# Private_CPU_SerDes.net
KiCad netlist of a schematic drawn in Altium Designer
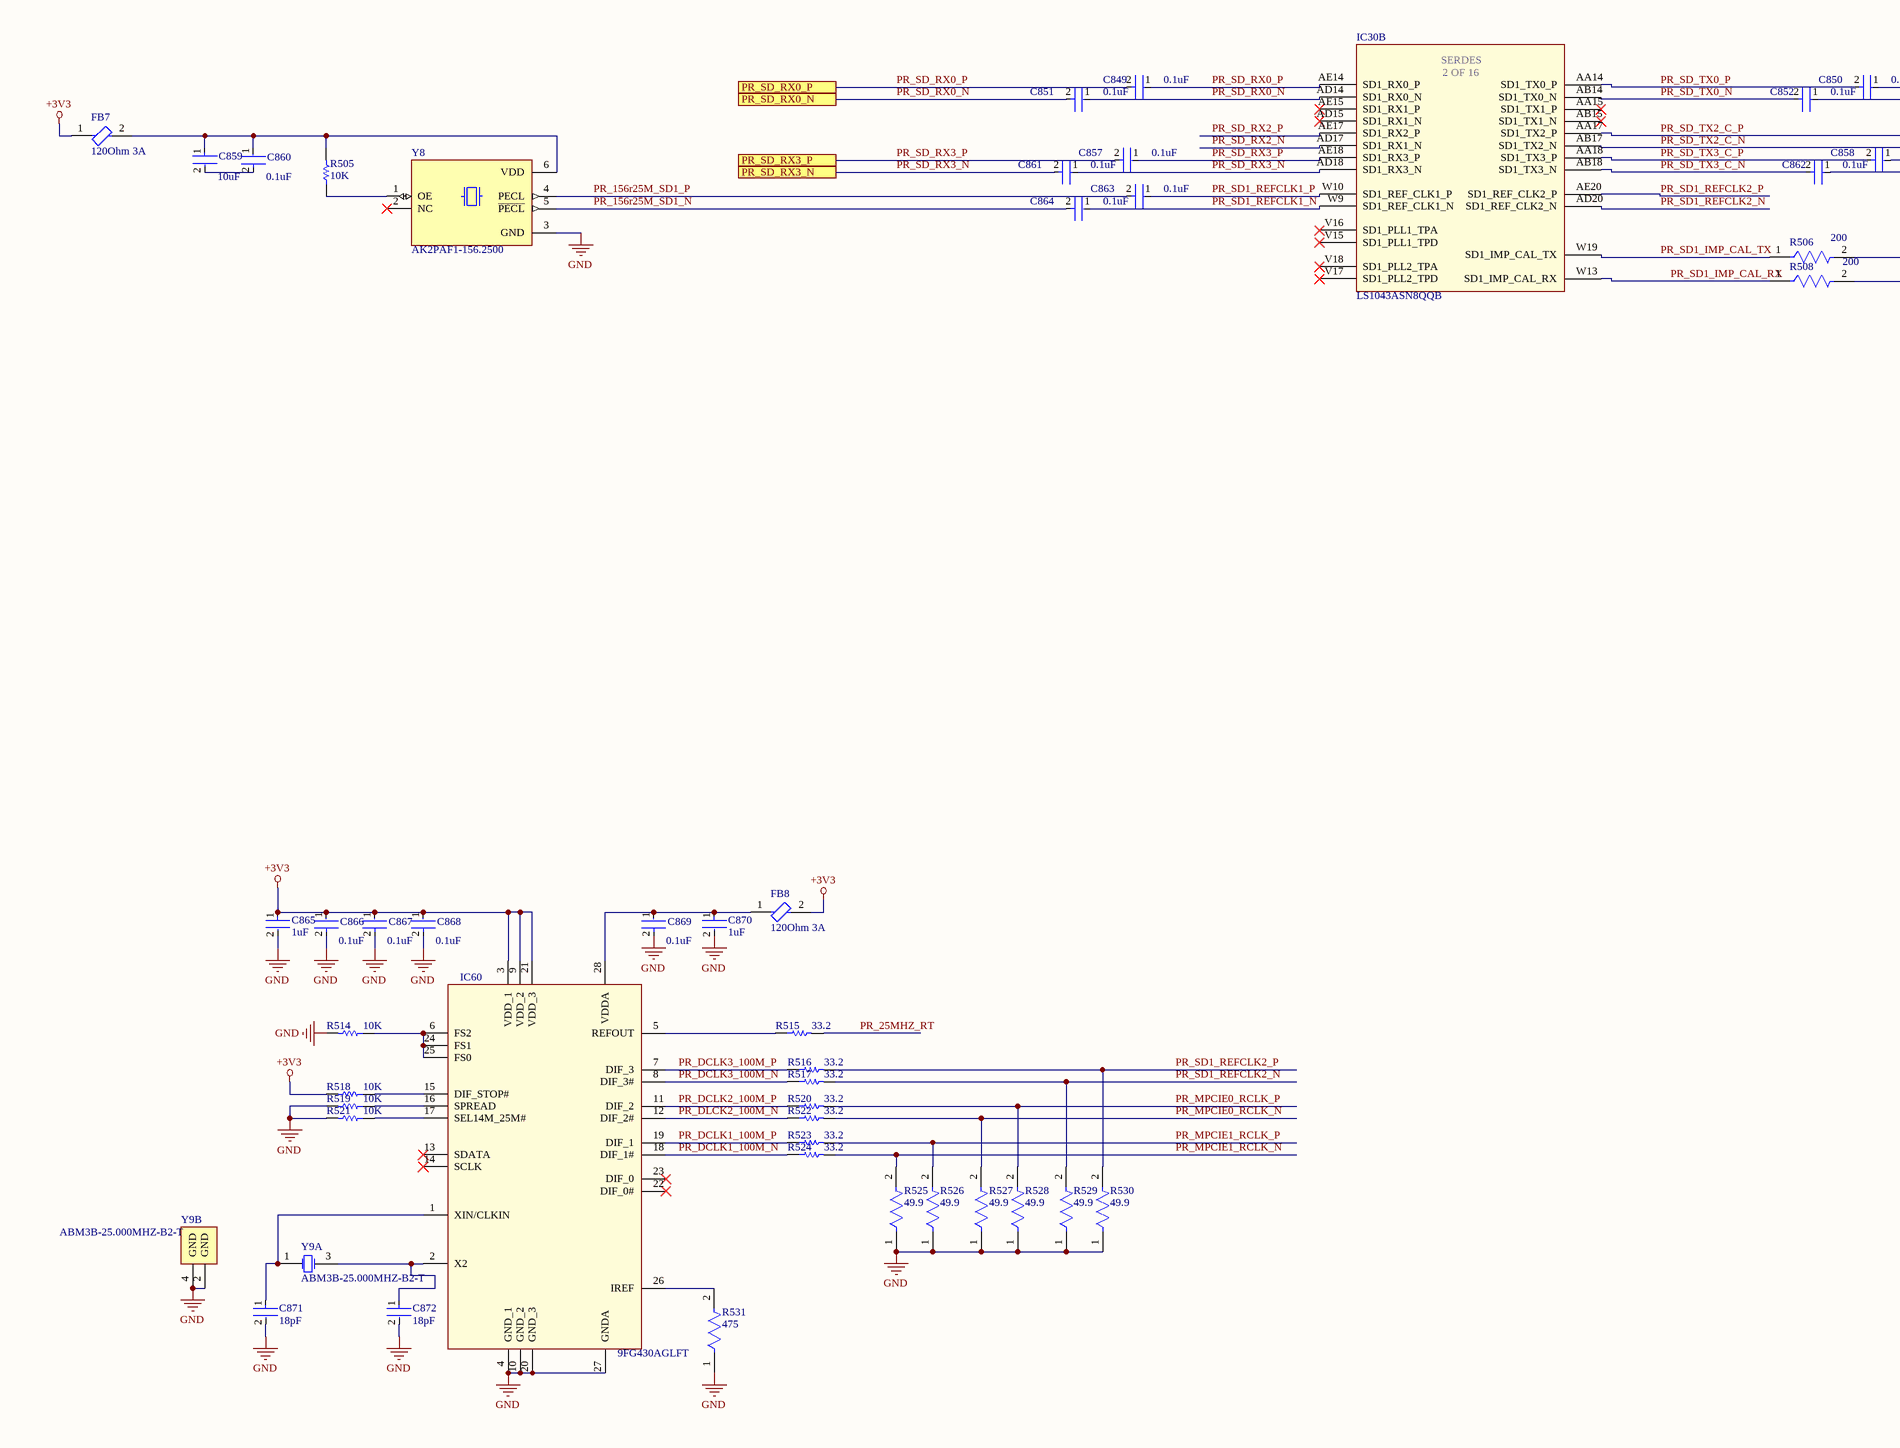
[diagram p0: Private_CPU_SerDes.SchDoc, left]
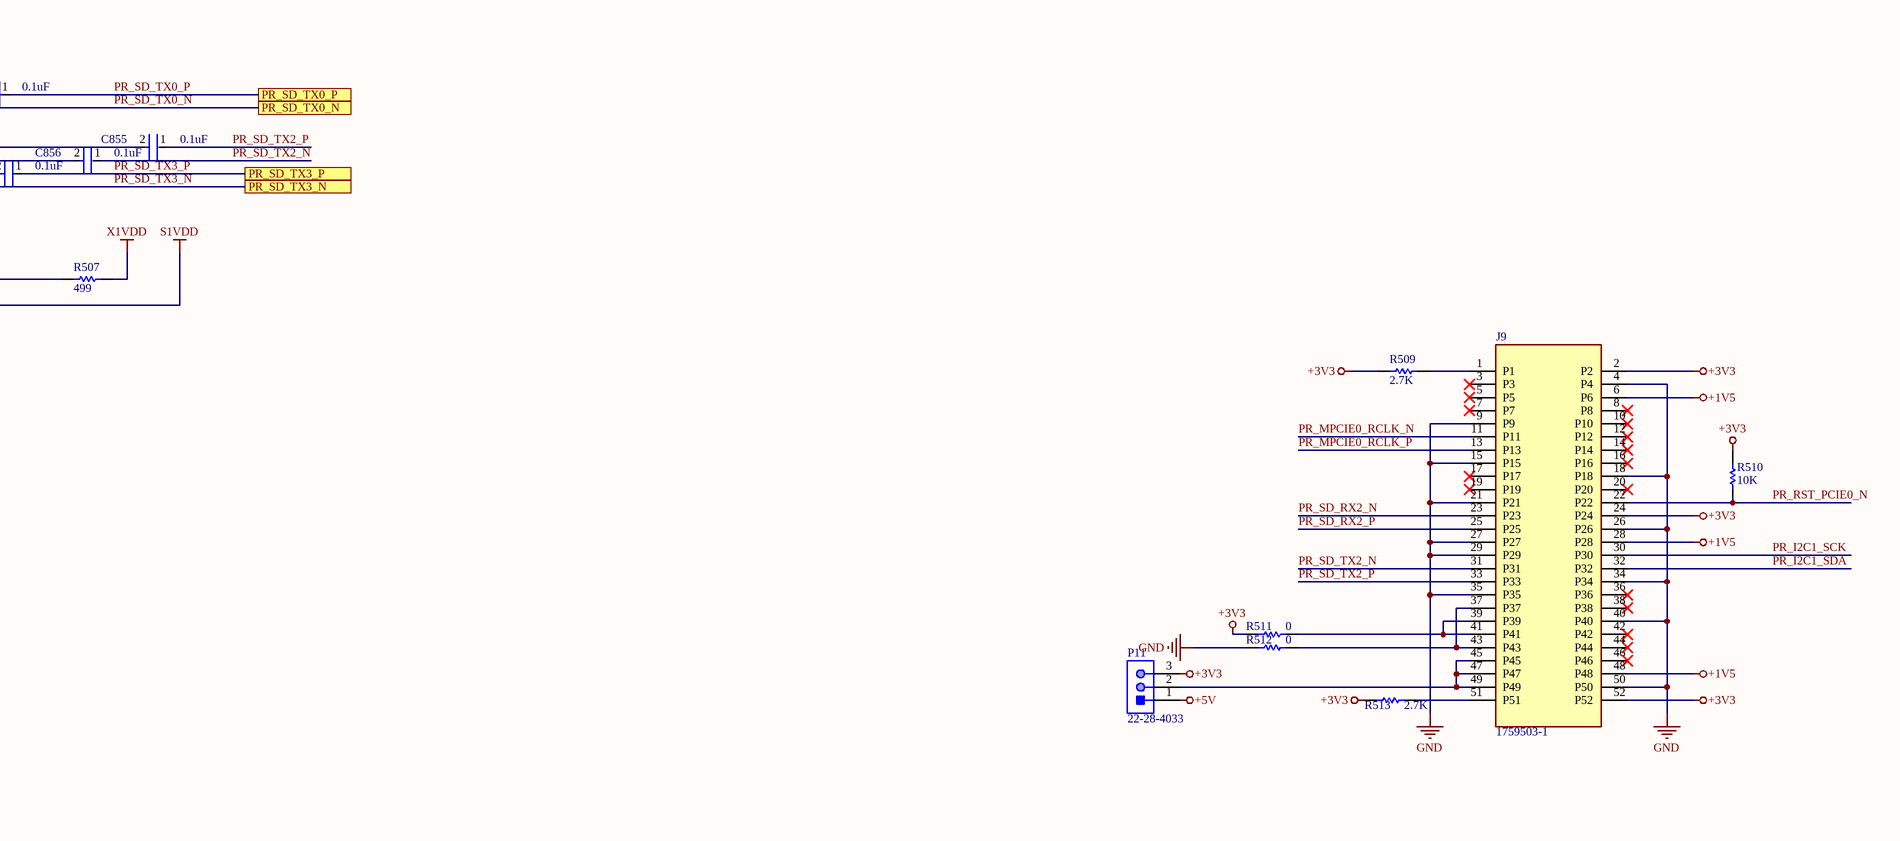
[diagram p1: Private_CPU_SerDes.SchDoc, right]

(export (version "E")
  (design (tool "Eeschema 10.0.6"))
  (components
    (comp (ref "C849")
      (value "0.1uF")
      (footprint "FP-GRM15-MFG")
      (description "CAP CER 0.1UF 16V X7R 0402")
      (fields (field (name "MANUFACTURER PART NUMBER") "GRM155R71C104KA88D") (field (name "TOLERANCE") "10%"))
      (libsource (lib "Altium Content Vault") (part "236180d848d6139a670b325ea6854c9"))
    )
    (comp (ref "C850")
      (value "0.1uF")
      (footprint "FP-GRM15-MFG")
      (description "CAP CER 0.1UF 16V X7R 0402")
      (fields (field (name "MANUFACTURER PART NUMBER") "GRM155R71C104KA88D") (field (name "TOLERANCE") "10%"))
      (libsource (lib "Altium Content Vault") (part "236180d848d6139a670b325ea6854c9"))
    )
    (comp (ref "C851")
      (value "0.1uF")
      (footprint "FP-GRM15-MFG")
      (description "CAP CER 0.1UF 16V X7R 0402")
      (fields (field (name "MANUFACTURER PART NUMBER") "GRM155R71C104KA88D") (field (name "TOLERANCE") "10%"))
      (libsource (lib "Altium Content Vault") (part "236180d848d6139a670b325ea6854c9"))
    )
    (comp (ref "C852")
      (value "0.1uF")
      (footprint "FP-GRM15-MFG")
      (description "CAP CER 0.1UF 16V X7R 0402")
      (fields (field (name "MANUFACTURER PART NUMBER") "GRM155R71C104KA88D") (field (name "TOLERANCE") "10%"))
      (libsource (lib "Altium Content Vault") (part "236180d848d6139a670b325ea6854c9"))
    )
    (comp (ref "C855")
      (value "0.1uF")
      (footprint "FP-GRM15-MFG")
      (description "CAP CER 0.1UF 16V X7R 0402")
      (fields (field (name "MANUFACTURER PART NUMBER") "GRM155R71C104KA88D") (field (name "TOLERANCE") "10%"))
      (libsource (lib "Altium Content Vault") (part "236180d848d6139a670b325ea6854c9"))
    )
    (comp (ref "C856")
      (value "0.1uF")
      (footprint "FP-GRM15-MFG")
      (description "CAP CER 0.1UF 16V X7R 0402")
      (fields (field (name "MANUFACTURER PART NUMBER") "GRM155R71C104KA88D") (field (name "TOLERANCE") "10%"))
      (libsource (lib "Altium Content Vault") (part "236180d848d6139a670b325ea6854c9"))
    )
    (comp (ref "C857")
      (value "0.1uF")
      (footprint "FP-GRM15-MFG")
      (description "CAP CER 0.1UF 16V X7R 0402")
      (fields (field (name "MANUFACTURER PART NUMBER") "GRM155R71C104KA88D") (field (name "TOLERANCE") "10%"))
      (libsource (lib "Altium Content Vault") (part "236180d848d6139a670b325ea6854c9"))
    )
    (comp (ref "C858")
      (value "0.1uF")
      (footprint "FP-GRM15-MFG")
      (description "CAP CER 0.1UF 16V X7R 0402")
      (fields (field (name "MANUFACTURER PART NUMBER") "GRM155R71C104KA88D") (field (name "TOLERANCE") "10%"))
      (libsource (lib "Altium Content Vault") (part "236180d848d6139a670b325ea6854c9"))
    )
    (comp (ref "C859")
      (value "10uF")
      (footprint "FP-C0805C-DG-MFG")
      (description "CAP CER 10UF 10V X5R 0805")
      (fields (field (name "TOLERANCE") "10%") (field (name "MANUFACTURER PART NUMBER") "C0805C106K8PACTU"))
      (libsource (lib "Altium Content Vault") (part "11868f565c42a9108669ba33697ecf6"))
    )
    (comp (ref "C860")
      (value "0.1uF")
      (footprint "FP-GRM15-MFG")
      (description "CAP CER 0.1UF 16V X7R 0402")
      (fields (field (name "MANUFACTURER PART NUMBER") "GRM155R71C104KA88D") (field (name "TOLERANCE") "10%"))
      (libsource (lib "Altium Content Vault") (part "236180d848d6139a670b325ea6854c9"))
    )
    (comp (ref "C861")
      (value "0.1uF")
      (footprint "FP-GRM15-MFG")
      (description "CAP CER 0.1UF 16V X7R 0402")
      (fields (field (name "MANUFACTURER PART NUMBER") "GRM155R71C104KA88D") (field (name "TOLERANCE") "10%"))
      (libsource (lib "Altium Content Vault") (part "236180d848d6139a670b325ea6854c9"))
    )
    (comp (ref "C862")
      (value "0.1uF")
      (footprint "FP-GRM15-MFG")
      (description "CAP CER 0.1UF 16V X7R 0402")
      (fields (field (name "MANUFACTURER PART NUMBER") "GRM155R71C104KA88D") (field (name "TOLERANCE") "10%"))
      (libsource (lib "Altium Content Vault") (part "236180d848d6139a670b325ea6854c9"))
    )
    (comp (ref "C863")
      (value "0.1uF")
      (footprint "FP-GRM15-MFG")
      (description "CAP CER 0.1UF 16V X7R 0402")
      (fields (field (name "MANUFACTURER PART NUMBER") "GRM155R71C104KA88D") (field (name "TOLERANCE") "10%"))
      (libsource (lib "Altium Content Vault") (part "236180d848d6139a670b325ea6854c9"))
    )
    (comp (ref "C864")
      (value "0.1uF")
      (footprint "FP-GRM15-MFG")
      (description "CAP CER 0.1UF 16V X7R 0402")
      (fields (field (name "MANUFACTURER PART NUMBER") "GRM155R71C104KA88D") (field (name "TOLERANCE") "10%"))
      (libsource (lib "Altium Content Vault") (part "236180d848d6139a670b325ea6854c9"))
    )
    (comp (ref "C865")
      (value "1uF")
      (footprint "FP-GRM15-0_1-MFG")
      (description "CAP CER 1UF 10V X5R 0402")
      (fields
        (field (name "OCTOPART") "https://octopart.com/grm155r61a105ke15d-murata-197442")
        (field (name "MANUFACTURER PART NUMBER") "GRM155R61A105KE15D")
      )
      (libsource (lib "Altium Content Vault") (part "02cd4be3c70576c341d710602a673aa"))
    )
    (comp (ref "C866")
      (value "0.1uF")
      (footprint "FP-GRM15-MFG")
      (description "CAP CER 0.1UF 16V X7R 0402")
      (fields (field (name "MANUFACTURER PART NUMBER") "GRM155R71C104KA88D") (field (name "TOLERANCE") "10%"))
      (libsource (lib "Altium Content Vault") (part "236180d848d6139a670b325ea6854c9"))
    )
    (comp (ref "C867")
      (value "0.1uF")
      (footprint "FP-GRM15-MFG")
      (description "CAP CER 0.1UF 16V X7R 0402")
      (fields (field (name "MANUFACTURER PART NUMBER") "GRM155R71C104KA88D") (field (name "TOLERANCE") "10%"))
      (libsource (lib "Altium Content Vault") (part "236180d848d6139a670b325ea6854c9"))
    )
    (comp (ref "C868")
      (value "0.1uF")
      (footprint "FP-GRM15-MFG")
      (description "CAP CER 0.1UF 16V X7R 0402")
      (fields (field (name "MANUFACTURER PART NUMBER") "GRM155R71C104KA88D") (field (name "TOLERANCE") "10%"))
      (libsource (lib "Altium Content Vault") (part "236180d848d6139a670b325ea6854c9"))
    )
    (comp (ref "C869")
      (value "0.1uF")
      (footprint "FP-GRM15-MFG")
      (description "CAP CER 0.1UF 16V X7R 0402")
      (fields (field (name "MANUFACTURER PART NUMBER") "GRM155R71C104KA88D") (field (name "TOLERANCE") "10%"))
      (libsource (lib "Altium Content Vault") (part "236180d848d6139a670b325ea6854c9"))
    )
    (comp (ref "C870")
      (value "1uF")
      (footprint "FP-GRM15-0_1-MFG")
      (description "CAP CER 1UF 10V X5R 0402")
      (fields
        (field (name "OCTOPART") "https://octopart.com/grm155r61a105ke15d-murata-197442")
        (field (name "MANUFACTURER PART NUMBER") "GRM155R61A105KE15D")
      )
      (libsource (lib "Altium Content Vault") (part "02cd4be3c70576c341d710602a673aa"))
    )
    (comp (ref "C871")
      (value "18pF")
      (footprint "FP-C0402-BB-MFG")
      (description "CAP CER 18PF 50V 5% NP0 0402")
      (fields (field (name "MANUFACTURER PART NUMBER") "C0402C180J5GACTU") (field (name "TOLERANCE") "0.05"))
      (libsource (lib "Altium Content Vault") (part "b4654b650e69147ec39a6b967a45e02"))
    )
    (comp (ref "C872")
      (value "18pF")
      (footprint "FP-C0402-BB-MFG")
      (description "CAP CER 18PF 50V 5% NP0 0402")
      (fields (field (name "MANUFACTURER PART NUMBER") "C0402C180J5GACTU") (field (name "TOLERANCE") "0.05"))
      (libsource (lib "Altium Content Vault") (part "b4654b650e69147ec39a6b967a45e02"))
    )
    (comp (ref "FB7")
      (value "120Ohm 3A")
      (footprint "FP-BLM18-0_15-t0_5-d1_2-MFG")
      (description "Chip Ferrite Bead, 0603, 120Ω @ 100MHz, 25%, 0.025Ω, 3A")
      (fields (field (name "TOLERANCE") "25%"))
      (libsource (lib "Altium Content Vault") (part "5f30dd21d616792df468990f7003faa"))
    )
    (comp (ref "FB8")
      (value "120Ohm 3A")
      (footprint "FP-BLM18-0_15-t0_5-d1_2-MFG")
      (description "Chip Ferrite Bead, 0603, 120Ω @ 100MHz, 25%, 0.025Ω, 3A")
      (fields (field (name "TOLERANCE") "25%"))
      (libsource (lib "Altium Content Vault") (part "5f30dd21d616792df468990f7003faa"))
    )
    (comp (ref "IC30")
      (value "LS1043ASN8QQB")
      (footprint "SamacSys:BGA780C80P28X28_2300X2300X261")
      (description "Integrated Circuit")
      (fields (field (name "MOUSER PART NUMBER") "771-LS1043ASN8QQB"))
      (libsource (lib "SamacSys") (part "LS1043ASN8QQB"))
    )
    (comp (ref "IC60")
      (value "9FG430AGLFT")
      (footprint "SamacSys:SOP65P640X120-28N")
      (description "Integrated Circuit")
      (libsource (lib "SamacSys") (part "9FG430AGLFT"))
    )
    (comp (ref "J9")
      (value "1759503-1")
      (footprint "1759503-1:TE_1759503-1")
      (description "mini PCI-E 8H Type I PKG G/F")
      (fields (field (name "MF") "{'manufacturer': u'TE Connectivity'}"))
      (libsource (lib "*") (part "1759503-1"))
    )
    (comp (ref "P11")
      (value "22-28-4033")
      (footprint "MOLX-22-28-4033_V")
      (description "Male Header, Pitch 2.54 mm, 1 x 3 Position, Height 8.38 mm, Tail Length 3.18 mm, RoHS, Bulk")
      (fields (field (name "MANUFACTURER") "Molex"))
      (libsource (lib "Altium Content Vault") (part "CN-1P-M-R3"))
    )
    (comp (ref "R505")
      (value "10K")
      (footprint "RESC1005X40X25LL05T05")
      (description "Chip Resistor, 10 KOhm, +/- 1%, 0.1 W, -55 to 155 degC, 0402 (1005 Metric), RoHS, Tape and Reel")
      (fields (field (name "TOLERANCE") "1%") (field (name "MANUFACTURER") "Panasonic"))
      (libsource (lib "Altium Content Vault") (part "RES-2"))
    )
    (comp (ref "R506")
      (value "200")
      (footprint "FP-CRCW0402-e3-IPC_C")
      (description "RES Thick Film, 200Ω, 1%, 0.063W, 100ppm/°C, 0402")
      (fields (field (name "TOLERANCE") "1%"))
      (libsource (lib "Altium Content Vault") (part "1029c3af85768c4190bb7ad29bc67b5"))
    )
    (comp (ref "R507")
      (value "499")
      (footprint "RESC1005X40X25LL05T05")
      (fields (field (name "MANUFACTURER") "Panasonic") (field (name "PART NUMBER") "ERJ-2RKF4990X"))
      (libsource (lib "Altium Content Vault") (part "RES"))
    )
    (comp (ref "R508")
      (value "200")
      (footprint "FP-CRCW0402-e3-IPC_C")
      (description "RES Thick Film, 200Ω, 1%, 0.063W, 100ppm/°C, 0402")
      (fields (field (name "TOLERANCE") "1%"))
      (libsource (lib "Altium Content Vault") (part "1029c3af85768c4190bb7ad29bc67b5"))
    )
    (comp (ref "R509")
      (value "2.7K")
      (footprint "RESC1005X40X25NL05T05")
      (fields (field (name "PART NUMBER") "ERJ2RKF2701X") (field (name "MANUFACTURER") "Panasonic"))
      (libsource (lib "Altium Content Vault") (part "RES"))
    )
    (comp (ref "R510")
      (value "10K")
      (footprint "RESC1005X40X25LL05T05")
      (description "Chip Resistor, 10 KOhm, +/- 1%, 0.1 W, -55 to 155 degC, 0402 (1005 Metric), RoHS, Tape and Reel")
      (fields (field (name "TOLERANCE") "1%") (field (name "MANUFACTURER") "Panasonic"))
      (libsource (lib "Altium Content Vault") (part "RES-2"))
    )
    (comp (ref "R511")
      (value "0")
      (footprint "RESC2013X50X30LL20T20")
      (fields (field (name "MANUFACTURER") "Vishay Dale") (field (name "PART NUMBER") "CRCW08050000Z0EA"))
      (libsource (lib "Altium Content Vault") (part "RES"))
    )
    (comp (ref "R512")
      (value "0")
      (footprint "RESC2013X50X30LL20T20")
      (fields (field (name "MANUFACTURER") "Vishay Dale") (field (name "PART NUMBER") "CRCW08050000Z0EA"))
      (libsource (lib "Altium Content Vault") (part "RES"))
    )
    (comp (ref "R513")
      (value "2.7K")
      (footprint "RESC1005X40X25NL05T05")
      (fields (field (name "PART NUMBER") "ERJ2RKF2701X") (field (name "MANUFACTURER") "Panasonic"))
      (libsource (lib "Altium Content Vault") (part "RES"))
    )
    (comp (ref "R514")
      (value "10K")
      (footprint "RESC1005X40X25LL05T05")
      (description "Chip Resistor, 10 KOhm, +/- 1%, 0.1 W, -55 to 155 degC, 0402 (1005 Metric), RoHS, Tape and Reel")
      (fields (field (name "TOLERANCE") "1%") (field (name "MANUFACTURER") "Panasonic"))
      (libsource (lib "Altium Content Vault") (part "RES-2"))
    )
    (comp (ref "R515")
      (value "33.2")
      (footprint "RESC1005X40X25LL05T05")
      (fields (field (name "PART NUMBER") "CRCW040233R2FKED") (field (name "MANUFACTURER") "Vishay Dale"))
      (libsource (lib "Altium Content Vault") (part "RES"))
    )
    (comp (ref "R516")
      (value "33.2")
      (footprint "RESC1005X40X25LL05T05")
      (fields (field (name "PART NUMBER") "CRCW040233R2FKED") (field (name "MANUFACTURER") "Vishay Dale"))
      (libsource (lib "Altium Content Vault") (part "RES"))
    )
    (comp (ref "R517")
      (value "33.2")
      (footprint "RESC1005X40X25LL05T05")
      (fields (field (name "PART NUMBER") "CRCW040233R2FKED") (field (name "MANUFACTURER") "Vishay Dale"))
      (libsource (lib "Altium Content Vault") (part "RES"))
    )
    (comp (ref "R518")
      (value "10K")
      (footprint "RESC1005X40X25LL05T05")
      (description "Chip Resistor, 10 KOhm, +/- 1%, 0.1 W, -55 to 155 degC, 0402 (1005 Metric), RoHS, Tape and Reel")
      (fields (field (name "TOLERANCE") "1%") (field (name "MANUFACTURER") "Panasonic"))
      (libsource (lib "Altium Content Vault") (part "RES-2"))
    )
    (comp (ref "R519")
      (value "10K")
      (footprint "RESC1005X40X25LL05T05")
      (description "Chip Resistor, 10 KOhm, +/- 1%, 0.1 W, -55 to 155 degC, 0402 (1005 Metric), RoHS, Tape and Reel")
      (fields (field (name "TOLERANCE") "1%") (field (name "MANUFACTURER") "Panasonic"))
      (libsource (lib "Altium Content Vault") (part "RES-2"))
    )
    (comp (ref "R520")
      (value "33.2")
      (footprint "RESC1005X40X25LL05T05")
      (fields (field (name "PART NUMBER") "CRCW040233R2FKED") (field (name "MANUFACTURER") "Vishay Dale"))
      (libsource (lib "Altium Content Vault") (part "RES"))
    )
    (comp (ref "R521")
      (value "10K")
      (footprint "RESC1005X40X25LL05T05")
      (description "Chip Resistor, 10 KOhm, +/- 1%, 0.1 W, -55 to 155 degC, 0402 (1005 Metric), RoHS, Tape and Reel")
      (fields (field (name "TOLERANCE") "1%") (field (name "MANUFACTURER") "Panasonic"))
      (libsource (lib "Altium Content Vault") (part "RES-2"))
    )
    (comp (ref "R522")
      (value "33.2")
      (footprint "RESC1005X40X25LL05T05")
      (fields (field (name "PART NUMBER") "CRCW040233R2FKED") (field (name "MANUFACTURER") "Vishay Dale"))
      (libsource (lib "Altium Content Vault") (part "RES"))
    )
    (comp (ref "R523")
      (value "33.2")
      (footprint "RESC1005X40X25LL05T05")
      (fields (field (name "PART NUMBER") "CRCW040233R2FKED") (field (name "MANUFACTURER") "Vishay Dale"))
      (libsource (lib "Altium Content Vault") (part "RES"))
    )
    (comp (ref "R524")
      (value "33.2")
      (footprint "RESC1005X40X25LL05T05")
      (fields (field (name "PART NUMBER") "CRCW040233R2FKED") (field (name "MANUFACTURER") "Vishay Dale"))
      (libsource (lib "Altium Content Vault") (part "RES"))
    )
    (comp (ref "R525")
      (value "49.9")
      (footprint "FP-CRCW0402-e3-MFG")
      (description "RES Thick Film, 49.9Ω, 1%, 0.063W, 100ppm/°C, 0402")
      (fields (field (name "TOLERANCE") "1%"))
      (libsource (lib "Altium Content Vault") (part "1029c3af85768c4190bb7ad29bc67b5"))
    )
    (comp (ref "R526")
      (value "49.9")
      (footprint "FP-CRCW0402-e3-MFG")
      (description "RES Thick Film, 49.9Ω, 1%, 0.063W, 100ppm/°C, 0402")
      (fields (field (name "TOLERANCE") "1%"))
      (libsource (lib "Altium Content Vault") (part "1029c3af85768c4190bb7ad29bc67b5"))
    )
    (comp (ref "R527")
      (value "49.9")
      (footprint "FP-CRCW0402-e3-MFG")
      (description "RES Thick Film, 49.9Ω, 1%, 0.063W, 100ppm/°C, 0402")
      (fields (field (name "TOLERANCE") "1%"))
      (libsource (lib "Altium Content Vault") (part "1029c3af85768c4190bb7ad29bc67b5"))
    )
    (comp (ref "R528")
      (value "49.9")
      (footprint "FP-CRCW0402-e3-MFG")
      (description "RES Thick Film, 49.9Ω, 1%, 0.063W, 100ppm/°C, 0402")
      (fields (field (name "TOLERANCE") "1%"))
      (libsource (lib "Altium Content Vault") (part "1029c3af85768c4190bb7ad29bc67b5"))
    )
    (comp (ref "R529")
      (value "49.9")
      (footprint "FP-CRCW0402-e3-MFG")
      (description "RES Thick Film, 49.9Ω, 1%, 0.063W, 100ppm/°C, 0402")
      (fields (field (name "TOLERANCE") "1%"))
      (libsource (lib "Altium Content Vault") (part "1029c3af85768c4190bb7ad29bc67b5"))
    )
    (comp (ref "R530")
      (value "49.9")
      (footprint "FP-CRCW0402-e3-MFG")
      (description "RES Thick Film, 49.9Ω, 1%, 0.063W, 100ppm/°C, 0402")
      (fields (field (name "TOLERANCE") "1%"))
      (libsource (lib "Altium Content Vault") (part "1029c3af85768c4190bb7ad29bc67b5"))
    )
    (comp (ref "R531")
      (value "475")
      (footprint "FP-CRCW0603-e3-IPC_C")
      (description "RES Thick Film, 475Ω, 1%, 0.1W, 100ppm/°C, 0603")
      (fields (field (name "TOLERANCE") "1%"))
      (libsource (lib "Altium Content Vault") (part "1029c3af85768c4190bb7ad29bc67b5"))
    )
    (comp (ref "Y8")
      (value "AK2PAF1-156.2500")
      (footprint "AK2PAF1-156.2500:XTAL_AK2PAF1-156.2500")
      (description "XTAL OSC XO 156.25MHZ 3.3V LVPEC.   MANUFACTURER: ABRACON")
      (fields (field (name "MF") "{'manufacturer': u'Abracon LLC'}"))
      (libsource (lib "*") (part "AK2PAF1-156.2500"))
    )
    (comp (ref "Y9")
      (value "ABM3B-25.000MHZ-B2-T")
      (footprint "ABRA-ABM3B-4_V")
      (description "Crystal, SMD, 25.000000MHz Stab=50ppm 18.0pF")
      (fields (field (name "MANUFACTURER") "Abracon"))
      (libsource (lib "") (part "ABRA-ABM3B-4_1"))
    )
  )
  (nets
    (net (code "1") (name "+1V5") (class "Default")
      (node (ref "J9") (pin "28") (pinfunction "P28_28") (pintype "passive"))
      (node (ref "J9") (pin "48") (pinfunction "P48_48") (pintype "passive"))
      (node (ref "J9") (pin "6") (pinfunction "P6_6") (pintype "passive"))
    )
    (net (code "2") (name "+3V3") (class "Default")
      (node (ref "C865") (pin "1") (pinfunction "1_1") (pintype "passive"))
      (node (ref "C866") (pin "1") (pinfunction "1_1") (pintype "passive"))
      (node (ref "C867") (pin "1") (pinfunction "1_1") (pintype "passive"))
      (node (ref "C868") (pin "1") (pinfunction "1_1") (pintype "passive"))
      (node (ref "FB7") (pin "1") (pinfunction "1_1") (pintype "passive"))
      (node (ref "FB8") (pin "2") (pinfunction "2_2") (pintype "passive"))
      (node (ref "IC60") (pin "21") (pinfunction "VDD_3_21") (pintype "passive"))
      (node (ref "IC60") (pin "3") (pinfunction "VDD_1_3") (pintype "passive"))
      (node (ref "IC60") (pin "9") (pinfunction "VDD_2_9") (pintype "passive"))
      (node (ref "J9") (pin "2") (pinfunction "P2_2") (pintype "passive"))
      (node (ref "J9") (pin "24") (pinfunction "P24_24") (pintype "passive"))
      (node (ref "J9") (pin "52") (pinfunction "P52_52") (pintype "passive"))
      (node (ref "P11") (pin "3") (pinfunction "3_3") (pintype "passive"))
      (node (ref "R509") (pin "2") (pinfunction "2_2") (pintype "passive"))
      (node (ref "R510") (pin "2") (pinfunction "2_2") (pintype "passive"))
      (node (ref "R511") (pin "1") (pinfunction "1_1") (pintype "passive"))
      (node (ref "R513") (pin "2") (pinfunction "2_2") (pintype "passive"))
      (node (ref "R518") (pin "2") (pinfunction "2_2") (pintype "passive"))
    )
    (net (code "3") (name "+5V") (class "Default")
      (node (ref "P11") (pin "1") (pinfunction "1_1") (pintype "passive"))
    )
    (net (code "4") (name "/PR_25MHZ_RT") (class "Default")
      (node (ref "R515") (pin "2") (pinfunction "2_2") (pintype "passive"))
    )
    (net (code "5") (name "/PR_156r25M_SD1_N") (class "Default")
      (node (ref "C864") (pin "2") (pinfunction "2_2") (pintype "passive"))
      (node (ref "Y8") (pin "5") (pinfunction "~{PECL}_5") (pintype "output"))
    )
    (net (code "6") (name "/PR_156r25M_SD1_P") (class "Default")
      (node (ref "C863") (pin "2") (pinfunction "2_2") (pintype "passive"))
      (node (ref "Y8") (pin "4") (pinfunction "PECL_4") (pintype "output"))
    )
    (net (code "7") (name "/PR_DCLK1_100M_N") (class "Default")
      (node (ref "IC60") (pin "18") (pinfunction "DIF_1#_18") (pintype "passive"))
      (node (ref "R524") (pin "1") (pinfunction "1_1") (pintype "passive"))
    )
    (net (code "8") (name "/PR_DCLK1_100M_P") (class "Default")
      (node (ref "IC60") (pin "19") (pinfunction "DIF_1_19") (pintype "passive"))
      (node (ref "R523") (pin "1") (pinfunction "1_1") (pintype "passive"))
    )
    (net (code "9") (name "/PR_DCLK2_100M_P") (class "Default")
      (node (ref "IC60") (pin "11") (pinfunction "DIF_2_11") (pintype "passive"))
      (node (ref "R520") (pin "1") (pinfunction "1_1") (pintype "passive"))
    )
    (net (code "10") (name "/PR_DCLK3_100M_N") (class "Default")
      (node (ref "IC60") (pin "8") (pinfunction "DIF_3#_8") (pintype "passive"))
      (node (ref "R517") (pin "1") (pinfunction "1_1") (pintype "passive"))
    )
    (net (code "11") (name "/PR_DCLK3_100M_P") (class "Default")
      (node (ref "IC60") (pin "7") (pinfunction "DIF_3_7") (pintype "passive"))
      (node (ref "R516") (pin "1") (pinfunction "1_1") (pintype "passive"))
    )
    (net (code "12") (name "/PR_DLCK2_100M_N") (class "Default")
      (node (ref "IC60") (pin "12") (pinfunction "DIF_2#_12") (pintype "passive"))
      (node (ref "R522") (pin "1") (pinfunction "1_1") (pintype "passive"))
    )
    (net (code "13") (name "/PR_I2C1_SCK") (class "Default")
      (node (ref "J9") (pin "30") (pinfunction "P30_30") (pintype "passive"))
    )
    (net (code "14") (name "/PR_I2C1_SDA") (class "Default")
      (node (ref "J9") (pin "32") (pinfunction "P32_32") (pintype "passive"))
    )
    (net (code "15") (name "/PR_MPCIE0_RCLK_N") (class "Default")
      (node (ref "J9") (pin "11") (pinfunction "P11_11") (pintype "passive"))
      (node (ref "R522") (pin "2") (pinfunction "2_2") (pintype "passive"))
      (node (ref "R527") (pin "2") (pinfunction "2_2") (pintype "passive"))
    )
    (net (code "16") (name "/PR_MPCIE0_RCLK_P") (class "Default")
      (node (ref "J9") (pin "13") (pinfunction "P13_13") (pintype "passive"))
      (node (ref "R520") (pin "2") (pinfunction "2_2") (pintype "passive"))
      (node (ref "R528") (pin "2") (pinfunction "2_2") (pintype "passive"))
    )
    (net (code "17") (name "/PR_MPCIE1_RCLK_N") (class "Default")
      (node (ref "R524") (pin "2") (pinfunction "2_2") (pintype "passive"))
      (node (ref "R525") (pin "2") (pinfunction "2_2") (pintype "passive"))
    )
    (net (code "18") (name "/PR_MPCIE1_RCLK_P") (class "Default")
      (node (ref "R523") (pin "2") (pinfunction "2_2") (pintype "passive"))
      (node (ref "R526") (pin "2") (pinfunction "2_2") (pintype "passive"))
    )
    (net (code "19") (name "/PR_RST_PCIE0_N") (class "Default")
      (node (ref "J9") (pin "22") (pinfunction "P22_22") (pintype "passive"))
      (node (ref "R510") (pin "1") (pinfunction "1_1") (pintype "passive"))
    )
    (net (code "20") (name "/PR_SD1_IMP_CAL_RX") (class "Default")
      (node (ref "IC30") (pin "W13") (pinfunction "SD1_IMP_CAL_RX_W13") (pintype "passive"))
      (node (ref "R508") (pin "1") (pinfunction "1_1") (pintype "passive"))
    )
    (net (code "21") (name "/PR_SD1_IMP_CAL_TX") (class "Default")
      (node (ref "IC30") (pin "W19") (pinfunction "SD1_IMP_CAL_TX_W19") (pintype "passive"))
      (node (ref "R506") (pin "1") (pinfunction "1_1") (pintype "passive"))
    )
    (net (code "22") (name "/PR_SD1_REFCLK1_N") (class "Default")
      (node (ref "C864") (pin "1") (pinfunction "1_1") (pintype "passive"))
      (node (ref "IC30") (pin "W9") (pinfunction "SD1_REF_CLK1_N_W9") (pintype "passive"))
    )
    (net (code "23") (name "/PR_SD1_REFCLK1_P") (class "Default")
      (node (ref "C863") (pin "1") (pinfunction "1_1") (pintype "passive"))
      (node (ref "IC30") (pin "W10") (pinfunction "SD1_REF_CLK1_P_W10") (pintype "passive"))
    )
    (net (code "24") (name "/PR_SD1_REFCLK2_N") (class "Default")
      (node (ref "IC30") (pin "AD20") (pinfunction "SD1_REF_CLK2_N_AD20") (pintype "passive"))
      (node (ref "R517") (pin "2") (pinfunction "2_2") (pintype "passive"))
      (node (ref "R529") (pin "2") (pinfunction "2_2") (pintype "passive"))
    )
    (net (code "25") (name "/PR_SD1_REFCLK2_P") (class "Default")
      (node (ref "IC30") (pin "AE20") (pinfunction "SD1_REF_CLK2_P_AE20") (pintype "passive"))
      (node (ref "R516") (pin "2") (pinfunction "2_2") (pintype "passive"))
      (node (ref "R530") (pin "2") (pinfunction "2_2") (pintype "passive"))
    )
    (net (code "26") (name "/PR_SD_RX0_N") (class "Default")
      (node (ref "C851") (pin "1") (pinfunction "1_1") (pintype "passive"))
      (node (ref "C851") (pin "2") (pinfunction "2_2") (pintype "passive"))
      (node (ref "IC30") (pin "AD14") (pinfunction "SD1_RX0_N_AD14") (pintype "passive"))
    )
    (net (code "27") (name "/PR_SD_RX0_P") (class "Default")
      (node (ref "C849") (pin "1") (pinfunction "1_1") (pintype "passive"))
      (node (ref "C849") (pin "2") (pinfunction "2_2") (pintype "passive"))
      (node (ref "IC30") (pin "AE14") (pinfunction "SD1_RX0_P_AE14") (pintype "passive"))
    )
    (net (code "28") (name "/PR_SD_RX2_N") (class "Default")
      (node (ref "IC30") (pin "AD17") (pinfunction "SD1_RX1_N_AD17") (pintype "passive"))
      (node (ref "J9") (pin "23") (pinfunction "P23_23") (pintype "passive"))
    )
    (net (code "29") (name "/PR_SD_RX2_P") (class "Default")
      (node (ref "IC30") (pin "AE17") (pinfunction "SD1_RX2_P_AE17") (pintype "passive"))
      (node (ref "J9") (pin "25") (pinfunction "P25_25") (pintype "passive"))
    )
    (net (code "30") (name "/PR_SD_RX3_N") (class "Default")
      (node (ref "C861") (pin "1") (pinfunction "1_1") (pintype "passive"))
      (node (ref "C861") (pin "2") (pinfunction "2_2") (pintype "passive"))
      (node (ref "IC30") (pin "AD18") (pinfunction "SD1_RX3_N_AD18") (pintype "passive"))
    )
    (net (code "31") (name "/PR_SD_RX3_P") (class "Default")
      (node (ref "C857") (pin "1") (pinfunction "1_1") (pintype "passive"))
      (node (ref "C857") (pin "2") (pinfunction "2_2") (pintype "passive"))
      (node (ref "IC30") (pin "AE18") (pinfunction "SD1_RX3_P_AE18") (pintype "passive"))
    )
    (net (code "32") (name "/PR_SD_TX0_N") (class "Default")
      (node (ref "C852") (pin "1") (pinfunction "1_1") (pintype "passive"))
      (node (ref "C852") (pin "2") (pinfunction "2_2") (pintype "passive"))
      (node (ref "IC30") (pin "AB14") (pinfunction "SD1_TX0_N_AB14") (pintype "passive"))
    )
    (net (code "33") (name "/PR_SD_TX0_P") (class "Default")
      (node (ref "C850") (pin "1") (pinfunction "1_1") (pintype "passive"))
      (node (ref "C850") (pin "2") (pinfunction "2_2") (pintype "passive"))
      (node (ref "IC30") (pin "AA14") (pinfunction "SD1_TX0_P_AA14") (pintype "passive"))
    )
    (net (code "34") (name "/PR_SD_TX2_C_N") (class "Default")
      (node (ref "C856") (pin "2") (pinfunction "2_2") (pintype "passive"))
      (node (ref "IC30") (pin "AB17") (pinfunction "SD1_TX2_N_AB17") (pintype "passive"))
    )
    (net (code "35") (name "/PR_SD_TX2_C_P") (class "Default")
      (node (ref "C855") (pin "2") (pinfunction "2_2") (pintype "passive"))
      (node (ref "IC30") (pin "AA17") (pinfunction "SD1_TX2_P_AA17") (pintype "passive"))
    )
    (net (code "36") (name "/PR_SD_TX2_N") (class "Default")
      (node (ref "C856") (pin "1") (pinfunction "1_1") (pintype "passive"))
      (node (ref "J9") (pin "31") (pinfunction "P31_31") (pintype "passive"))
    )
    (net (code "37") (name "/PR_SD_TX2_P") (class "Default")
      (node (ref "C855") (pin "1") (pinfunction "1_1") (pintype "passive"))
      (node (ref "J9") (pin "33") (pinfunction "P33_33") (pintype "passive"))
    )
    (net (code "38") (name "/PR_SD_TX3_C_N") (class "Default")
      (node (ref "C862") (pin "2") (pinfunction "2_2") (pintype "passive"))
      (node (ref "IC30") (pin "AB18") (pinfunction "SD1_TX3_N_AB18") (pintype "passive"))
    )
    (net (code "39") (name "/PR_SD_TX3_C_P") (class "Default")
      (node (ref "C858") (pin "2") (pinfunction "2_2") (pintype "passive"))
      (node (ref "IC30") (pin "AA18") (pinfunction "SD1_TX3_P_AA18") (pintype "passive"))
    )
    (net (code "40") (name "/PR_SD_TX3_N") (class "Default")
      (node (ref "C862") (pin "1") (pinfunction "1_1") (pintype "passive"))
    )
    (net (code "41") (name "/PR_SD_TX3_P") (class "Default")
      (node (ref "C858") (pin "1") (pinfunction "1_1") (pintype "passive"))
    )
    (net (code "42") (name "GND") (class "Default")
      (node (ref "C865") (pin "2") (pinfunction "2_2") (pintype "passive"))
      (node (ref "C866") (pin "2") (pinfunction "2_2") (pintype "passive"))
      (node (ref "C867") (pin "2") (pinfunction "2_2") (pintype "passive"))
      (node (ref "C868") (pin "2") (pinfunction "2_2") (pintype "passive"))
      (node (ref "C869") (pin "2") (pinfunction "2_2") (pintype "passive"))
      (node (ref "C870") (pin "2") (pinfunction "2_2") (pintype "passive"))
      (node (ref "C871") (pin "2") (pinfunction "2_2") (pintype "passive"))
      (node (ref "C872") (pin "2") (pinfunction "2_2") (pintype "passive"))
      (node (ref "IC60") (pin "10") (pinfunction "GND_2_10") (pintype "passive"))
      (node (ref "IC60") (pin "20") (pinfunction "GND_3_20") (pintype "passive"))
      (node (ref "IC60") (pin "27") (pinfunction "GNDA_27") (pintype "passive"))
      (node (ref "IC60") (pin "4") (pinfunction "GND_1_4") (pintype "passive"))
      (node (ref "J9") (pin "15") (pinfunction "P15_15") (pintype "passive"))
      (node (ref "J9") (pin "18") (pinfunction "P18_18") (pintype "passive"))
      (node (ref "J9") (pin "21") (pinfunction "P21_21") (pintype "passive"))
      (node (ref "J9") (pin "26") (pinfunction "P26_26") (pintype "passive"))
      (node (ref "J9") (pin "27") (pinfunction "P27_27") (pintype "passive"))
      (node (ref "J9") (pin "29") (pinfunction "P29_29") (pintype "passive"))
      (node (ref "J9") (pin "34") (pinfunction "P34_34") (pintype "passive"))
      (node (ref "J9") (pin "35") (pinfunction "P35_35") (pintype "passive"))
      (node (ref "J9") (pin "4") (pinfunction "P4_4") (pintype "passive"))
      (node (ref "J9") (pin "40") (pinfunction "P40_40") (pintype "passive"))
      (node (ref "J9") (pin "50") (pinfunction "P50_50") (pintype "passive"))
      (node (ref "J9") (pin "9") (pinfunction "P9_9") (pintype "passive"))
      (node (ref "R512") (pin "1") (pinfunction "1_1") (pintype "passive"))
      (node (ref "R514") (pin "2") (pinfunction "2_2") (pintype "passive"))
      (node (ref "R519") (pin "2") (pinfunction "2_2") (pintype "passive"))
      (node (ref "R521") (pin "2") (pinfunction "2_2") (pintype "passive"))
      (node (ref "R525") (pin "1") (pinfunction "1_1") (pintype "passive"))
      (node (ref "R526") (pin "1") (pinfunction "1_1") (pintype "passive"))
      (node (ref "R527") (pin "1") (pinfunction "1_1") (pintype "passive"))
      (node (ref "R528") (pin "1") (pinfunction "1_1") (pintype "passive"))
      (node (ref "R529") (pin "1") (pinfunction "1_1") (pintype "passive"))
      (node (ref "R530") (pin "1") (pinfunction "1_1") (pintype "passive"))
      (node (ref "R531") (pin "1") (pinfunction "1_1") (pintype "passive"))
      (node (ref "Y8") (pin "3") (pinfunction "GND_3") (pintype "power_in"))
      (node (ref "Y9") (pin "2") (pinfunction "GND_2") (pintype "power_in"))
      (node (ref "Y9") (pin "4") (pinfunction "GND_4") (pintype "power_in"))
    )
    (net (code "43") (name "Net-(C859-Pad2)") (class "Default")
      (node (ref "C859") (pin "2") (pinfunction "2_2") (pintype "passive"))
      (node (ref "C860") (pin "2") (pinfunction "2_2") (pintype "passive"))
    )
    (net (code "44") (name "Net-(IC60-DIF_STOP#)") (class "Default")
      (node (ref "IC60") (pin "15") (pinfunction "DIF_STOP#_15") (pintype "passive"))
      (node (ref "R518") (pin "1") (pinfunction "1_1") (pintype "passive"))
    )
    (net (code "45") (name "Net-(IC60-FS0)") (class "Default")
      (node (ref "IC60") (pin "24") (pinfunction "FS1_24") (pintype "passive"))
      (node (ref "IC60") (pin "25") (pinfunction "FS0_25") (pintype "passive"))
      (node (ref "IC60") (pin "6") (pinfunction "FS2_6") (pintype "passive"))
      (node (ref "R514") (pin "1") (pinfunction "1_1") (pintype "passive"))
    )
    (net (code "46") (name "Net-(IC60-IREF)") (class "Default")
      (node (ref "IC60") (pin "26") (pinfunction "IREF_26") (pintype "passive"))
      (node (ref "R531") (pin "2") (pinfunction "2_2") (pintype "passive"))
    )
    (net (code "47") (name "Net-(IC60-REFOUT)") (class "Default")
      (node (ref "IC60") (pin "5") (pinfunction "REFOUT_5") (pintype "passive"))
      (node (ref "R515") (pin "1") (pinfunction "1_1") (pintype "passive"))
    )
    (net (code "48") (name "Net-(IC60-SEL14M_25M#)") (class "Default")
      (node (ref "IC60") (pin "17") (pinfunction "SEL14M_25M#_17") (pintype "passive"))
      (node (ref "R521") (pin "1") (pinfunction "1_1") (pintype "passive"))
    )
    (net (code "49") (name "Net-(IC60-SPREAD)") (class "Default")
      (node (ref "IC60") (pin "16") (pinfunction "SPREAD_16") (pintype "passive"))
      (node (ref "R519") (pin "1") (pinfunction "1_1") (pintype "passive"))
    )
    (net (code "50") (name "Net-(IC60-VDDA)") (class "Default")
      (node (ref "C869") (pin "1") (pinfunction "1_1") (pintype "passive"))
      (node (ref "C870") (pin "1") (pinfunction "1_1") (pintype "passive"))
      (node (ref "FB8") (pin "1") (pinfunction "1_1") (pintype "passive"))
      (node (ref "IC60") (pin "28") (pinfunction "VDDA_28") (pintype "passive"))
    )
    (net (code "51") (name "Net-(IC60-X2)") (class "Default")
      (node (ref "C872") (pin "1") (pinfunction "1_1") (pintype "passive"))
      (node (ref "IC60") (pin "2") (pinfunction "X2_2") (pintype "passive"))
      (node (ref "Y9") (pin "3") (pinfunction "X2_3") (pintype "passive"))
    )
    (net (code "52") (name "Net-(IC60-XIN{slash}CLKIN)") (class "Default")
      (node (ref "C871") (pin "1") (pinfunction "1_1") (pintype "passive"))
      (node (ref "IC60") (pin "1") (pinfunction "XIN/CLKIN_1") (pintype "passive"))
      (node (ref "Y9") (pin "1") (pinfunction "X1_1") (pintype "passive"))
    )
    (net (code "53") (name "Net-(J9-P1)") (class "Default")
      (node (ref "J9") (pin "1") (pinfunction "P1_1") (pintype "passive"))
      (node (ref "R509") (pin "1") (pinfunction "1_1") (pintype "passive"))
    )
    (net (code "54") (name "Net-(J9-P37)") (class "Default")
      (node (ref "J9") (pin "37") (pinfunction "P37_37") (pintype "passive"))
      (node (ref "J9") (pin "43") (pinfunction "P43_43") (pintype "passive"))
      (node (ref "R512") (pin "2") (pinfunction "2_2") (pintype "passive"))
    )
    (net (code "55") (name "Net-(J9-P39)") (class "Default")
      (node (ref "J9") (pin "39") (pinfunction "P39_39") (pintype "passive"))
      (node (ref "J9") (pin "41") (pinfunction "P41_41") (pintype "passive"))
      (node (ref "R511") (pin "2") (pinfunction "2_2") (pintype "passive"))
    )
    (net (code "56") (name "Net-(J9-P45)") (class "Default")
      (node (ref "J9") (pin "45") (pinfunction "P45_45") (pintype "passive"))
      (node (ref "J9") (pin "47") (pinfunction "P47_47") (pintype "passive"))
      (node (ref "J9") (pin "49") (pinfunction "P49_49") (pintype "passive"))
      (node (ref "P11") (pin "2") (pinfunction "2_2") (pintype "passive"))
    )
    (net (code "57") (name "Net-(J9-P51)") (class "Default")
      (node (ref "J9") (pin "51") (pinfunction "P51_51") (pintype "passive"))
      (node (ref "R513") (pin "1") (pinfunction "1_1") (pintype "passive"))
    )
    (net (code "58") (name "Net-(R506-Pad2)") (class "Default")
      (node (ref "R506") (pin "2") (pinfunction "2_2") (pintype "passive"))
      (node (ref "R507") (pin "1") (pinfunction "1_1") (pintype "passive"))
    )
    (net (code "59") (name "Net-(Y8-OE)") (class "Default")
      (node (ref "R505") (pin "1") (pinfunction "1_1") (pintype "passive"))
      (node (ref "Y8") (pin "1") (pinfunction "OE_1") (pintype "bidirectional"))
    )
    (net (code "60") (name "Net-(Y8-VDD)") (class "Default")
      (node (ref "C859") (pin "1") (pinfunction "1_1") (pintype "passive"))
      (node (ref "C860") (pin "1") (pinfunction "1_1") (pintype "passive"))
      (node (ref "FB7") (pin "2") (pinfunction "2_2") (pintype "passive"))
      (node (ref "R505") (pin "2") (pinfunction "2_2") (pintype "passive"))
      (node (ref "Y8") (pin "6") (pinfunction "VDD_6") (pintype "power_in"))
    )
    (net (code "61") (name "S1VDD") (class "Default")
      (node (ref "R508") (pin "2") (pinfunction "2_2") (pintype "passive"))
    )
    (net (code "62") (name "X1VDD") (class "Default")
      (node (ref "R507") (pin "2") (pinfunction "2_2") (pintype "passive"))
    )
    (net (code "63") (name "unconnected-(IC30B-SD1_PLL1_TPA-PadV16)") (class "Default")
      (node (ref "IC30") (pin "V16") (pinfunction "SD1_PLL1_TPA_V16") (pintype "passive+no_connect"))
    )
    (net (code "64") (name "unconnected-(IC30B-SD1_PLL1_TPD-PadV15)") (class "Default")
      (node (ref "IC30") (pin "V15") (pinfunction "SD1_PLL1_TPD_V15") (pintype "passive+no_connect"))
    )
    (net (code "65") (name "unconnected-(IC30B-SD1_PLL2_TPA-PadV18)") (class "Default")
      (node (ref "IC30") (pin "V18") (pinfunction "SD1_PLL2_TPA_V18") (pintype "passive+no_connect"))
    )
    (net (code "66") (name "unconnected-(IC30B-SD1_PLL2_TPD-PadV17)") (class "Default")
      (node (ref "IC30") (pin "V17") (pinfunction "SD1_PLL2_TPD_V17") (pintype "passive+no_connect"))
    )
    (net (code "67") (name "unconnected-(IC30B-SD1_RX1_N-PadAD15)") (class "Default")
      (node (ref "IC30") (pin "AD15") (pinfunction "SD1_RX1_N_AD15") (pintype "passive+no_connect"))
    )
    (net (code "68") (name "unconnected-(IC30B-SD1_RX1_P-PadAE15)") (class "Default")
      (node (ref "IC30") (pin "AE15") (pinfunction "SD1_RX1_P_AE15") (pintype "passive+no_connect"))
    )
    (net (code "69") (name "unconnected-(IC30B-SD1_TX1_N-PadAB15)") (class "Default")
      (node (ref "IC30") (pin "AB15") (pinfunction "SD1_TX1_N_AB15") (pintype "passive+no_connect"))
    )
    (net (code "70") (name "unconnected-(IC30B-SD1_TX1_P-PadAA15)") (class "Default")
      (node (ref "IC30") (pin "AA15") (pinfunction "SD1_TX1_P_AA15") (pintype "passive+no_connect"))
    )
    (net (code "71") (name "unconnected-(IC60-DIF_0#-Pad22)") (class "Default")
      (node (ref "IC60") (pin "22") (pinfunction "DIF_0#_22") (pintype "passive+no_connect"))
    )
    (net (code "72") (name "unconnected-(IC60-DIF_0-Pad23)") (class "Default")
      (node (ref "IC60") (pin "23") (pinfunction "DIF_0_23") (pintype "passive+no_connect"))
    )
    (net (code "73") (name "unconnected-(IC60-SCLK-Pad14)") (class "Default")
      (node (ref "IC60") (pin "14") (pinfunction "SCLK_14") (pintype "passive+no_connect"))
    )
    (net (code "74") (name "unconnected-(IC60-SDATA-Pad13)") (class "Default")
      (node (ref "IC60") (pin "13") (pinfunction "SDATA_13") (pintype "passive+no_connect"))
    )
    (net (code "75") (name "unconnected-(J9-P3-Pad3)") (class "Default")
      (node (ref "J9") (pin "3") (pinfunction "P3_3") (pintype "passive+no_connect"))
    )
    (net (code "76") (name "unconnected-(J9-P5-Pad5)") (class "Default")
      (node (ref "J9") (pin "5") (pinfunction "P5_5") (pintype "passive+no_connect"))
    )
    (net (code "77") (name "unconnected-(J9-P7-Pad7)") (class "Default")
      (node (ref "J9") (pin "7") (pinfunction "P7_7") (pintype "passive+no_connect"))
    )
    (net (code "78") (name "unconnected-(J9-P8-Pad8)") (class "Default")
      (node (ref "J9") (pin "8") (pinfunction "P8_8") (pintype "passive+no_connect"))
    )
    (net (code "79") (name "unconnected-(J9-P10-Pad10)") (class "Default")
      (node (ref "J9") (pin "10") (pinfunction "P10_10") (pintype "passive+no_connect"))
    )
    (net (code "80") (name "unconnected-(J9-P12-Pad12)") (class "Default")
      (node (ref "J9") (pin "12") (pinfunction "P12_12") (pintype "passive+no_connect"))
    )
    (net (code "81") (name "unconnected-(J9-P14-Pad14)") (class "Default")
      (node (ref "J9") (pin "14") (pinfunction "P14_14") (pintype "passive+no_connect"))
    )
    (net (code "82") (name "unconnected-(J9-P16-Pad16)") (class "Default")
      (node (ref "J9") (pin "16") (pinfunction "P16_16") (pintype "passive+no_connect"))
    )
    (net (code "83") (name "unconnected-(J9-P17-Pad17)") (class "Default")
      (node (ref "J9") (pin "17") (pinfunction "P17_17") (pintype "passive+no_connect"))
    )
    (net (code "84") (name "unconnected-(J9-P19-Pad19)") (class "Default")
      (node (ref "J9") (pin "19") (pinfunction "P19_19") (pintype "passive+no_connect"))
    )
    (net (code "85") (name "unconnected-(J9-P20-Pad20)") (class "Default")
      (node (ref "J9") (pin "20") (pinfunction "P20_20") (pintype "passive+no_connect"))
    )
    (net (code "86") (name "unconnected-(J9-P36-Pad36)") (class "Default")
      (node (ref "J9") (pin "36") (pinfunction "P36_36") (pintype "passive+no_connect"))
    )
    (net (code "87") (name "unconnected-(J9-P38-Pad38)") (class "Default")
      (node (ref "J9") (pin "38") (pinfunction "P38_38") (pintype "passive+no_connect"))
    )
    (net (code "88") (name "unconnected-(J9-P42-Pad42)") (class "Default")
      (node (ref "J9") (pin "42") (pinfunction "P42_42") (pintype "passive+no_connect"))
    )
    (net (code "89") (name "unconnected-(J9-P44-Pad44)") (class "Default")
      (node (ref "J9") (pin "44") (pinfunction "P44_44") (pintype "passive+no_connect"))
    )
    (net (code "90") (name "unconnected-(J9-P46-Pad46)") (class "Default")
      (node (ref "J9") (pin "46") (pinfunction "P46_46") (pintype "passive+no_connect"))
    )
    (net (code "91") (name "unconnected-(Y8-NC-Pad2)") (class "Default")
      (node (ref "Y8") (pin "2") (pinfunction "NC_2") (pintype "passive+no_connect"))
    )
  )
)
